# ADC-DAC.net
KiCad netlist of a schematic drawn in Altium Designer
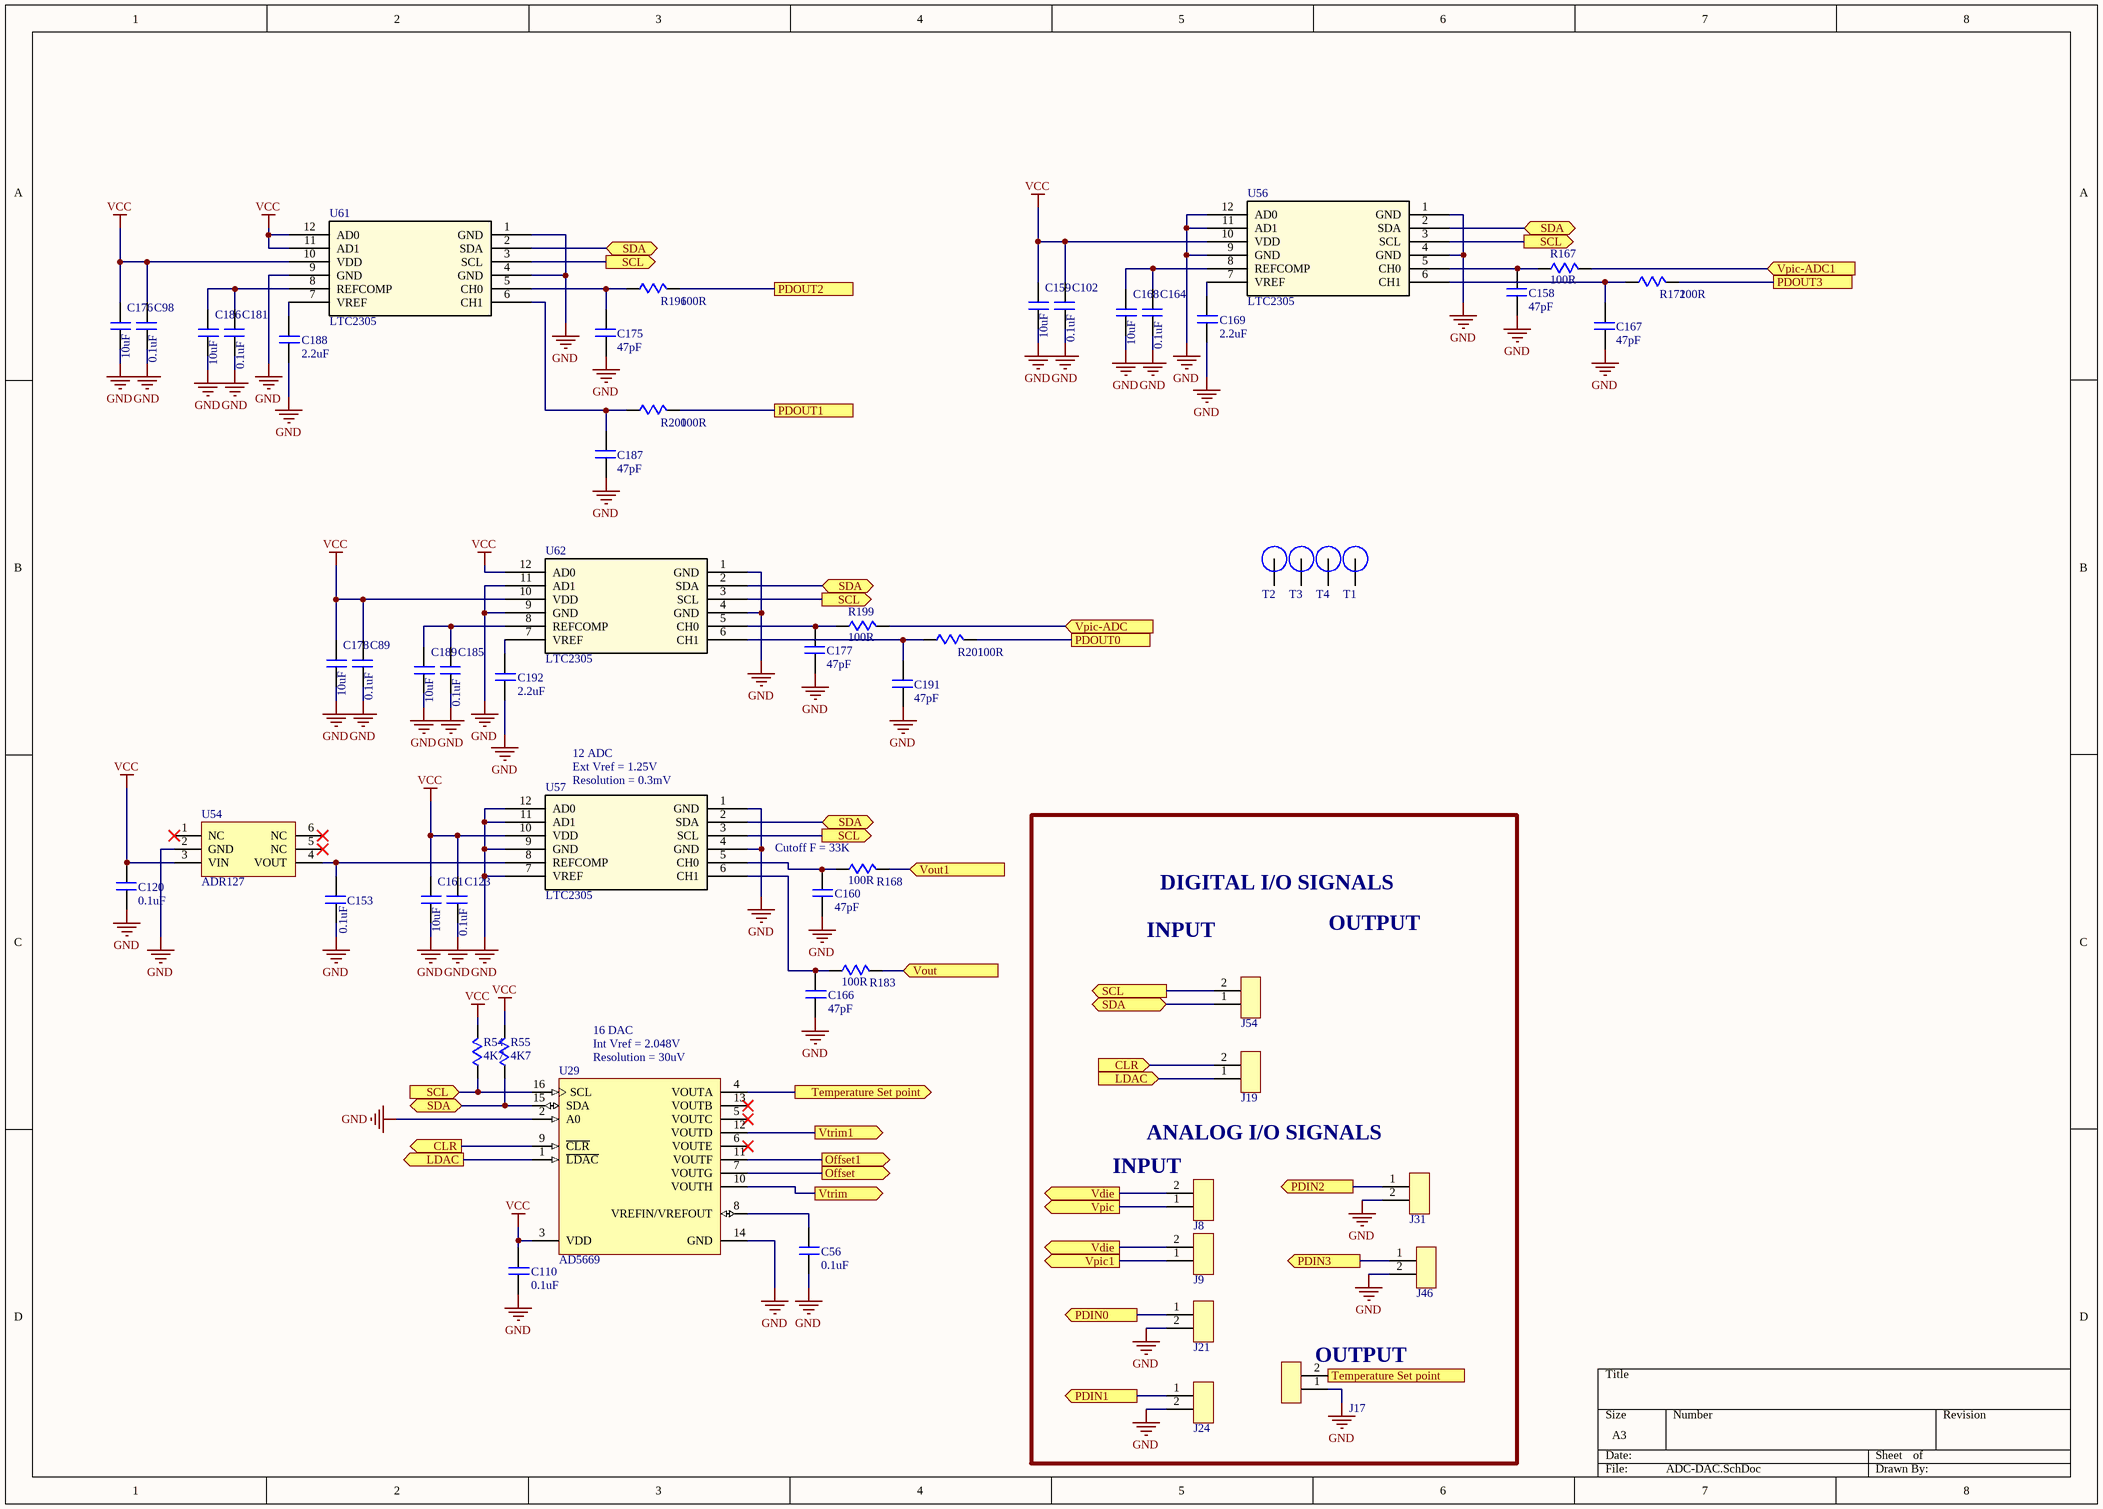
[diagram p0: ADC-DAC.SchDoc]

(export (version "E")
  (design (tool "Eeschema 10.0.6"))
  (components
    (comp (ref "C56")
      (value "0.1uF")
      (footprint "CAP0603")
      (description "50V 100nF X5R 卤10% 0603 Multilayer Ceramic Capacitors MLCC - SMD/SMT ROHS")
      (fields
        (field (name "MANUFACTURER") "TDK")
        (field (name "MANUFACTURER PART NUMBER") "C1608X5R1H104K080AA")
      )
      (libsource (lib "Pilot") (part "Capacitor 0.1uF"))
    )
    (comp (ref "C89")
      (value "0.1uF")
      (footprint "CAP0603")
      (description "50V 100nF X5R 卤10% 0603 Multilayer Ceramic Capacitors MLCC - SMD/SMT ROHS")
      (fields
        (field (name "MANUFACTURER") "TDK")
        (field (name "MANUFACTURER PART NUMBER") "C1608X5R1H104K080AA")
      )
      (libsource (lib "Pilot") (part "Capacitor 0.1uF"))
    )
    (comp (ref "C98")
      (value "0.1uF")
      (footprint "CAP0603")
      (description "50V 100nF X5R 卤10% 0603 Multilayer Ceramic Capacitors MLCC - SMD/SMT ROHS")
      (fields
        (field (name "MANUFACTURER") "TDK")
        (field (name "MANUFACTURER PART NUMBER") "C1608X5R1H104K080AA")
      )
      (libsource (lib "Pilot") (part "Capacitor 0.1uF"))
    )
    (comp (ref "C102")
      (value "0.1uF")
      (footprint "CAP0603")
      (description "50V 100nF X5R 卤10% 0603 Multilayer Ceramic Capacitors MLCC - SMD/SMT ROHS")
      (fields
        (field (name "MANUFACTURER") "TDK")
        (field (name "MANUFACTURER PART NUMBER") "C1608X5R1H104K080AA")
      )
      (libsource (lib "Pilot") (part "Capacitor 0.1uF"))
    )
    (comp (ref "C110")
      (value "0.1uF")
      (footprint "CAP0603")
      (description "50V 100nF X5R 卤10% 0603 Multilayer Ceramic Capacitors MLCC - SMD/SMT ROHS")
      (fields
        (field (name "MANUFACTURER") "TDK")
        (field (name "MANUFACTURER PART NUMBER") "C1608X5R1H104K080AA")
      )
      (libsource (lib "Pilot") (part "Capacitor 0.1uF"))
    )
    (comp (ref "C120")
      (value "0.1uF")
      (footprint "CAP0603")
      (description "50V 100nF X5R 卤10% 0603 Multilayer Ceramic Capacitors MLCC - SMD/SMT ROHS")
      (fields
        (field (name "MANUFACTURER") "TDK")
        (field (name "MANUFACTURER PART NUMBER") "C1608X5R1H104K080AA")
      )
      (libsource (lib "Pilot") (part "Capacitor 0.1uF"))
    )
    (comp (ref "C123")
      (value "0.1uF")
      (footprint "CAP0603")
      (description "50V 100nF X5R 卤10% 0603 Multilayer Ceramic Capacitors MLCC - SMD/SMT ROHS")
      (fields
        (field (name "MANUFACTURER") "TDK")
        (field (name "MANUFACTURER PART NUMBER") "C1608X5R1H104K080AA")
      )
      (libsource (lib "Pilot") (part "Capacitor 0.1uF"))
    )
    (comp (ref "C153")
      (value "0.1uF")
      (footprint "CAP0603")
      (description "50V 100nF X5R 卤10% 0603 Multilayer Ceramic Capacitors MLCC - SMD/SMT ROHS")
      (fields
        (field (name "MANUFACTURER") "TDK")
        (field (name "MANUFACTURER PART NUMBER") "C1608X5R1H104K080AA")
      )
      (libsource (lib "Pilot") (part "Capacitor 0.1uF"))
    )
    (comp (ref "C158")
      (value "47pF")
      (footprint "CAP0805")
      (description "Cap Cer 4.7PF 100V C0G/NP0 0805")
      (fields
        (field (name "MANUFACTURER") "Wurth Electronics")
        (field (name "MANUFACTURER PART NUMBER") "885012007096")
      )
      (libsource (lib "Pilot") (part "Capactior 47pF"))
    )
    (comp (ref "C159")
      (value "10uF")
      (footprint "CAP0805")
      (description "SMD Multilayer Ceramic Capacitor, 10 ï¿½F, 25 V, 0805 [2012 Metric], ï¿½ 10%, X7S")
      (fields
        (field (name "MANUFACTURER") "TDK")
        (field (name "MANUFACTURER PART NUMBER") "C2012X7S1E106K125AC")
      )
      (libsource (lib "Pilot") (part "Capacitor 10uF"))
    )
    (comp (ref "C160")
      (value "47pF")
      (footprint "CAP0805")
      (description "Cap Cer 4.7PF 100V C0G/NP0 0805")
      (fields
        (field (name "MANUFACTURER") "Wurth Electronics")
        (field (name "MANUFACTURER PART NUMBER") "885012007096")
      )
      (libsource (lib "Pilot") (part "Capactior 47pF"))
    )
    (comp (ref "C161")
      (value "10uF")
      (footprint "CAP0805")
      (description "SMD Multilayer Ceramic Capacitor, 10 ï¿½F, 25 V, 0805 [2012 Metric], ï¿½ 10%, X7S")
      (fields
        (field (name "MANUFACTURER") "TDK")
        (field (name "MANUFACTURER PART NUMBER") "C2012X7S1E106K125AC")
      )
      (libsource (lib "Pilot") (part "Capacitor 10uF"))
    )
    (comp (ref "C164")
      (value "0.1uF")
      (footprint "CAP0603")
      (description "50V 100nF X5R 卤10% 0603 Multilayer Ceramic Capacitors MLCC - SMD/SMT ROHS")
      (fields
        (field (name "MANUFACTURER") "TDK")
        (field (name "MANUFACTURER PART NUMBER") "C1608X5R1H104K080AA")
      )
      (libsource (lib "Pilot") (part "Capacitor 0.1uF"))
    )
    (comp (ref "C166")
      (value "47pF")
      (footprint "CAP0805")
      (description "Cap Cer 4.7PF 100V C0G/NP0 0805")
      (fields
        (field (name "MANUFACTURER") "Wurth Electronics")
        (field (name "MANUFACTURER PART NUMBER") "885012007096")
      )
      (libsource (lib "Pilot") (part "Capactior 47pF"))
    )
    (comp (ref "C167")
      (value "47pF")
      (footprint "CAP0805")
      (description "Cap Cer 4.7PF 100V C0G/NP0 0805")
      (fields
        (field (name "MANUFACTURER") "Wurth Electronics")
        (field (name "MANUFACTURER PART NUMBER") "885012007096")
      )
      (libsource (lib "Pilot") (part "Capactior 47pF"))
    )
    (comp (ref "C168")
      (value "10uF")
      (footprint "CAP0805")
      (description "SMD Multilayer Ceramic Capacitor, 10 ï¿½F, 25 V, 0805 [2012 Metric], ï¿½ 10%, X7S")
      (fields
        (field (name "MANUFACTURER") "TDK")
        (field (name "MANUFACTURER PART NUMBER") "C2012X7S1E106K125AC")
      )
      (libsource (lib "Pilot") (part "Capacitor 10uF"))
    )
    (comp (ref "C169")
      (value "2.2uF")
      (footprint "CAP0603")
      (description "Multilayer Ceramic Capacitors (High dielectric type), 16V, 2.2 uF, ± 20 %, 0603, X5R, RoHS")
      (fields
        (field (name "MANUFACTURER") "Taiyo Yuden")
        (field (name "MANUFACTURER PART NUMBER") "EMK107BJ225MA-T")
      )
      (libsource (lib "Pilot") (part "Capacitor 2.2uF"))
    )
    (comp (ref "C175")
      (value "47pF")
      (footprint "CAP0805")
      (description "Cap Cer 4.7PF 100V C0G/NP0 0805")
      (fields
        (field (name "MANUFACTURER") "Wurth Electronics")
        (field (name "MANUFACTURER PART NUMBER") "885012007096")
      )
      (libsource (lib "Pilot") (part "Capactior 47pF"))
    )
    (comp (ref "C176")
      (value "10uF")
      (footprint "CAP0805")
      (description "SMD Multilayer Ceramic Capacitor, 10 ï¿½F, 25 V, 0805 [2012 Metric], ï¿½ 10%, X7S")
      (fields
        (field (name "MANUFACTURER") "TDK")
        (field (name "MANUFACTURER PART NUMBER") "C2012X7S1E106K125AC")
      )
      (libsource (lib "Pilot") (part "Capacitor 10uF"))
    )
    (comp (ref "C177")
      (value "47pF")
      (footprint "CAP0805")
      (description "Cap Cer 4.7PF 100V C0G/NP0 0805")
      (fields
        (field (name "MANUFACTURER") "Wurth Electronics")
        (field (name "MANUFACTURER PART NUMBER") "885012007096")
      )
      (libsource (lib "Pilot") (part "Capactior 47pF"))
    )
    (comp (ref "C178")
      (value "10uF")
      (footprint "CAP0805")
      (description "SMD Multilayer Ceramic Capacitor, 10 ï¿½F, 25 V, 0805 [2012 Metric], ï¿½ 10%, X7S")
      (fields
        (field (name "MANUFACTURER") "TDK")
        (field (name "MANUFACTURER PART NUMBER") "C2012X7S1E106K125AC")
      )
      (libsource (lib "Pilot") (part "Capacitor 10uF"))
    )
    (comp (ref "C181")
      (value "0.1uF")
      (footprint "CAP0603")
      (description "50V 100nF X5R 卤10% 0603 Multilayer Ceramic Capacitors MLCC - SMD/SMT ROHS")
      (fields
        (field (name "MANUFACTURER") "TDK")
        (field (name "MANUFACTURER PART NUMBER") "C1608X5R1H104K080AA")
      )
      (libsource (lib "Pilot") (part "Capacitor 0.1uF"))
    )
    (comp (ref "C185")
      (value "0.1uF")
      (footprint "CAP0603")
      (description "50V 100nF X5R 卤10% 0603 Multilayer Ceramic Capacitors MLCC - SMD/SMT ROHS")
      (fields
        (field (name "MANUFACTURER") "TDK")
        (field (name "MANUFACTURER PART NUMBER") "C1608X5R1H104K080AA")
      )
      (libsource (lib "Pilot") (part "Capacitor 0.1uF"))
    )
    (comp (ref "C186")
      (value "10uF")
      (footprint "CAP0805")
      (description "SMD Multilayer Ceramic Capacitor, 10 ï¿½F, 25 V, 0805 [2012 Metric], ï¿½ 10%, X7S")
      (fields
        (field (name "MANUFACTURER") "TDK")
        (field (name "MANUFACTURER PART NUMBER") "C2012X7S1E106K125AC")
      )
      (libsource (lib "Pilot") (part "Capacitor 10uF"))
    )
    (comp (ref "C187")
      (value "47pF")
      (footprint "CAP0805")
      (description "Cap Cer 4.7PF 100V C0G/NP0 0805")
      (fields
        (field (name "MANUFACTURER") "Wurth Electronics")
        (field (name "MANUFACTURER PART NUMBER") "885012007096")
      )
      (libsource (lib "Pilot") (part "Capactior 47pF"))
    )
    (comp (ref "C188")
      (value "2.2uF")
      (footprint "CAP0603")
      (description "Multilayer Ceramic Capacitors (High dielectric type), 16V, 2.2 uF, ± 20 %, 0603, X5R, RoHS")
      (fields
        (field (name "MANUFACTURER") "Taiyo Yuden")
        (field (name "MANUFACTURER PART NUMBER") "EMK107BJ225MA-T")
      )
      (libsource (lib "Pilot") (part "Capacitor 2.2uF"))
    )
    (comp (ref "C189")
      (value "10uF")
      (footprint "CAP0805")
      (description "SMD Multilayer Ceramic Capacitor, 10 ï¿½F, 25 V, 0805 [2012 Metric], ï¿½ 10%, X7S")
      (fields
        (field (name "MANUFACTURER") "TDK")
        (field (name "MANUFACTURER PART NUMBER") "C2012X7S1E106K125AC")
      )
      (libsource (lib "Pilot") (part "Capacitor 10uF"))
    )
    (comp (ref "C191")
      (value "47pF")
      (footprint "CAP0805")
      (description "Cap Cer 4.7PF 100V C0G/NP0 0805")
      (fields
        (field (name "MANUFACTURER") "Wurth Electronics")
        (field (name "MANUFACTURER PART NUMBER") "885012007096")
      )
      (libsource (lib "Pilot") (part "Capactior 47pF"))
    )
    (comp (ref "C192")
      (value "2.2uF")
      (footprint "CAP0603")
      (description "Multilayer Ceramic Capacitors (High dielectric type), 16V, 2.2 uF, ± 20 %, 0603, X5R, RoHS")
      (fields
        (field (name "MANUFACTURER") "Taiyo Yuden")
        (field (name "MANUFACTURER PART NUMBER") "EMK107BJ225MA-T")
      )
      (libsource (lib "Pilot") (part "Capacitor 2.2uF"))
    )
    (comp (ref "J8")
      (value "Header1x2")
      (footprint "HEADER 1x2")
      (description "Conn Wire to Board HDR 2 POS 2.54mm Solder ST Thru-Hole Bulk")
      (fields (field (name "MANUFACTURER") "Molex") (field (name "MANUFACTURER PART NUMBER") "22-23-2022"))
      (libsource (lib "") (part "Header 1x2_1"))
    )
    (comp (ref "J9")
      (value "Header1x2")
      (footprint "HEADER 1x2")
      (description "Conn Wire to Board HDR 2 POS 2.54mm Solder ST Thru-Hole Bulk")
      (fields (field (name "MANUFACTURER") "Molex") (field (name "MANUFACTURER PART NUMBER") "22-23-2022"))
      (libsource (lib "") (part "Header 1x2_1"))
    )
    (comp (ref "J17")
      (value "Header1x2")
      (footprint "HEADER 1x2")
      (description "Conn Wire to Board HDR 2 POS 2.54mm Solder ST Thru-Hole Bulk")
      (fields (field (name "MANUFACTURER") "Molex") (field (name "MANUFACTURER PART NUMBER") "22-23-2022"))
      (libsource (lib "") (part "Header 1x2_2"))
    )
    (comp (ref "J19")
      (value "Header1x2")
      (footprint "HEADER 1x2")
      (description "Conn Wire to Board HDR 2 POS 2.54mm Solder ST Thru-Hole Bulk")
      (fields (field (name "MANUFACTURER") "Molex") (field (name "MANUFACTURER PART NUMBER") "22-23-2022"))
      (libsource (lib "") (part "Header 1x2_1"))
    )
    (comp (ref "J21")
      (value "Header1x2")
      (footprint "HEADER 1x2")
      (description "Conn Wire to Board HDR 2 POS 2.54mm Solder ST Thru-Hole Bulk")
      (fields (field (name "MANUFACTURER") "Molex") (field (name "MANUFACTURER PART NUMBER") "22-23-2022"))
      (libsource (lib "Pilot") (part "Header 1x2"))
    )
    (comp (ref "J24")
      (value "Header1x2")
      (footprint "HEADER 1x2")
      (description "Conn Wire to Board HDR 2 POS 2.54mm Solder ST Thru-Hole Bulk")
      (fields (field (name "MANUFACTURER") "Molex") (field (name "MANUFACTURER PART NUMBER") "22-23-2022"))
      (libsource (lib "Pilot") (part "Header 1x2"))
    )
    (comp (ref "J31")
      (value "Header1x2")
      (footprint "HEADER 1x2")
      (description "Conn Wire to Board HDR 2 POS 2.54mm Solder ST Thru-Hole Bulk")
      (fields (field (name "MANUFACTURER") "Molex") (field (name "MANUFACTURER PART NUMBER") "22-23-2022"))
      (libsource (lib "Pilot") (part "Header 1x2"))
    )
    (comp (ref "J46")
      (value "Header1x2")
      (footprint "HEADER 1x2")
      (description "Conn Wire to Board HDR 2 POS 2.54mm Solder ST Thru-Hole Bulk")
      (fields (field (name "MANUFACTURER") "Molex") (field (name "MANUFACTURER PART NUMBER") "22-23-2022"))
      (libsource (lib "Pilot") (part "Header 1x2"))
    )
    (comp (ref "J54")
      (value "Header1x2")
      (footprint "HEADER 1x2")
      (description "Conn Wire to Board HDR 2 POS 2.54mm Solder ST Thru-Hole Bulk")
      (fields (field (name "MANUFACTURER") "Molex") (field (name "MANUFACTURER PART NUMBER") "22-23-2022"))
      (libsource (lib "") (part "Header 1x2_1"))
    )
    (comp (ref "R54")
      (value "4K7")
      (footprint "RES0805")
      (description "Res Thin Film 0805 4.7K Ohm 0.1% 0.125W(1/8W) ±50ppm/C Epoxy Pad SMD T/R")
      (fields
        (field (name "MANUFACTURER") "Yageo")
        (field (name "MANUFACTURER PART NUMBER") "RT0805BRE074K7L")
      )
      (libsource (lib "Pilot") (part "Resistor 4.7K"))
    )
    (comp (ref "R55")
      (value "4K7")
      (footprint "RES0805")
      (description "Res Thin Film 0805 4.7K Ohm 0.1% 0.125W(1/8W) ±50ppm/C Epoxy Pad SMD T/R")
      (fields
        (field (name "MANUFACTURER") "Yageo")
        (field (name "MANUFACTURER PART NUMBER") "RT0805BRE074K7L")
      )
      (libsource (lib "Pilot") (part "Resistor 4.7K"))
    )
    (comp (ref "R167")
      (value "100R")
      (footprint "RES0805")
      (description "High Precision-High Stability Chip Resistor Thin Film 0805 100Ohm 0.5% Paper T/R")
      (fields
        (field (name "MANUFACTURER") "Yageo")
        (field (name "MANUFACTURER PART NUMBER") "RT0805DRE07100RL")
      )
      (libsource (lib "Pilot") (part "Resistor 100R"))
    )
    (comp (ref "R168")
      (value "100R")
      (footprint "RES0805")
      (description "High Precision-High Stability Chip Resistor Thin Film 0805 100Ohm 0.5% Paper T/R")
      (fields
        (field (name "MANUFACTURER") "Yageo")
        (field (name "MANUFACTURER PART NUMBER") "RT0805DRE07100RL")
      )
      (libsource (lib "Pilot") (part "Resistor 100R"))
    )
    (comp (ref "R172")
      (value "100R")
      (footprint "RES0805")
      (description "High Precision-High Stability Chip Resistor Thin Film 0805 100Ohm 0.5% Paper T/R")
      (fields
        (field (name "MANUFACTURER") "Yageo")
        (field (name "MANUFACTURER PART NUMBER") "RT0805DRE07100RL")
      )
      (libsource (lib "Pilot") (part "Resistor 100R"))
    )
    (comp (ref "R183")
      (value "100R")
      (footprint "RES0805")
      (description "High Precision-High Stability Chip Resistor Thin Film 0805 100Ohm 0.5% Paper T/R")
      (fields
        (field (name "MANUFACTURER") "Yageo")
        (field (name "MANUFACTURER PART NUMBER") "RT0805DRE07100RL")
      )
      (libsource (lib "Pilot") (part "Resistor 100R"))
    )
    (comp (ref "R196")
      (value "100R")
      (footprint "RES0805")
      (description "High Precision-High Stability Chip Resistor Thin Film 0805 100Ohm 0.5% Paper T/R")
      (fields
        (field (name "MANUFACTURER") "Yageo")
        (field (name "MANUFACTURER PART NUMBER") "RT0805DRE07100RL")
      )
      (libsource (lib "Pilot") (part "Resistor 100R"))
    )
    (comp (ref "R199")
      (value "100R")
      (footprint "RES0805")
      (description "High Precision-High Stability Chip Resistor Thin Film 0805 100Ohm 0.5% Paper T/R")
      (fields
        (field (name "MANUFACTURER") "Yageo")
        (field (name "MANUFACTURER PART NUMBER") "RT0805DRE07100RL")
      )
      (libsource (lib "Pilot") (part "Resistor 100R"))
    )
    (comp (ref "R200")
      (value "100R")
      (footprint "RES0805")
      (description "High Precision-High Stability Chip Resistor Thin Film 0805 100Ohm 0.5% Paper T/R")
      (fields
        (field (name "MANUFACTURER") "Yageo")
        (field (name "MANUFACTURER PART NUMBER") "RT0805DRE07100RL")
      )
      (libsource (lib "Pilot") (part "Resistor 100R"))
    )
    (comp (ref "R201")
      (value "100R")
      (footprint "RES0805")
      (description "High Precision-High Stability Chip Resistor Thin Film 0805 100Ohm 0.5% Paper T/R")
      (fields
        (field (name "MANUFACTURER") "Yageo")
        (field (name "MANUFACTURER PART NUMBER") "RT0805DRE07100RL")
      )
      (libsource (lib "Pilot") (part "Resistor 100R"))
    )
    (comp (ref "T1")
      (value "TP")
      (footprint "Hole 3.3mm")
      (libsource (lib "Pilot") (part "Mount hole 3.3mm"))
    )
    (comp (ref "T2")
      (value "TP")
      (footprint "Hole 3.3mm")
      (libsource (lib "Pilot") (part "Mount hole 3.3mm"))
    )
    (comp (ref "T3")
      (value "TP")
      (footprint "Hole 3.3mm")
      (libsource (lib "Pilot") (part "Mount hole 3.3mm"))
    )
    (comp (ref "T4")
      (value "TP")
      (footprint "Hole 3.3mm")
      (libsource (lib "Pilot") (part "Mount hole 3.3mm"))
    )
    (comp (ref "U29")
      (value "AD5669")
      (footprint "TSSOP16")
      (description "DAC 8-CH Resistor-String 16-bit 16-Pin TSSOP Tube")
      (fields
        (field (name "MANUFACTURER") "Analog Devices")
        (field (name "MANUFACTURER PART NUMBER") "AD5669RARUZ-1")
      )
      (libsource (lib "Pilot") (part "AD5669RARUZ-1"))
    )
    (comp (ref "U54")
      (value "ADR127")
      (footprint "TSOT6")
      (description "Precision, Micropower LD0 1.25 VOUT Voltage Reference in TSOT")
      (fields
        (field (name "MANUFACTURER") "Analog Devices")
        (field (name "MANUFACTURER PART NUMBER") "ADR127BUJZ-REEL7")
      )
      (libsource (lib "Pilot") (part "ADR127BUJZ-REEL7"))
    )
    (comp (ref "U56")
      (value "LTC2305")
      (footprint "MSOP12")
      (description "2-Channel Single ADC SAR 14ksps 12-bit Serial Automotive 12-Pin MSOP Tube")
      (fields
        (field (name "MANUFACTURER") "Analog Devices / Linear Technology")
        (field (name "MANUFACTURER PART NUMBER") "LTC2305CMS#PBF")
      )
      (libsource (lib "Pilot") (part "LTC2305CMS#PBF"))
    )
    (comp (ref "U57")
      (value "LTC2305")
      (footprint "MSOP12")
      (description "2-Channel Single ADC SAR 14ksps 12-bit Serial Automotive 12-Pin MSOP Tube")
      (fields
        (field (name "MANUFACTURER") "Analog Devices / Linear Technology")
        (field (name "MANUFACTURER PART NUMBER") "LTC2305CMS#PBF")
      )
      (libsource (lib "Pilot") (part "LTC2305CMS#PBF"))
    )
    (comp (ref "U61")
      (value "LTC2305")
      (footprint "MSOP12")
      (description "2-Channel Single ADC SAR 14ksps 12-bit Serial Automotive 12-Pin MSOP Tube")
      (fields
        (field (name "MANUFACTURER") "Analog Devices / Linear Technology")
        (field (name "MANUFACTURER PART NUMBER") "LTC2305CMS#PBF")
      )
      (libsource (lib "Pilot") (part "LTC2305CMS#PBF"))
    )
    (comp (ref "U62")
      (value "LTC2305")
      (footprint "MSOP12")
      (description "2-Channel Single ADC SAR 14ksps 12-bit Serial Automotive 12-Pin MSOP Tube")
      (fields
        (field (name "MANUFACTURER") "Analog Devices / Linear Technology")
        (field (name "MANUFACTURER PART NUMBER") "LTC2305CMS#PBF")
      )
      (libsource (lib "Pilot") (part "LTC2305CMS#PBF"))
    )
  )
  (nets
    (net (code "1") (name "/CLR") (class "Default")
      (node (ref "J19") (pin "2") (pinfunction "2_2") (pintype "passive"))
      (node (ref "U29") (pin "9") (pinfunction "~{CLR}_9") (pintype "input"))
    )
    (net (code "2") (name "/LDAC") (class "Default")
      (node (ref "J19") (pin "1") (pinfunction "1_1") (pintype "passive"))
      (node (ref "U29") (pin "1") (pinfunction "~{LDAC}_1") (pintype "input"))
    )
    (net (code "3") (name "/Offset") (class "Default")
      (node (ref "U29") (pin "7") (pinfunction "VOUTG_7") (pintype "tri_state"))
    )
    (net (code "4") (name "/Offset1") (class "Default")
      (node (ref "U29") (pin "11") (pinfunction "VOUTF_11") (pintype "tri_state"))
    )
    (net (code "5") (name "/PDIN0") (class "Default")
      (node (ref "J21") (pin "1") (pinfunction "1_1") (pintype "passive"))
    )
    (net (code "6") (name "/PDIN1") (class "Default")
      (node (ref "J24") (pin "1") (pinfunction "1_1") (pintype "passive"))
    )
    (net (code "7") (name "/PDIN2") (class "Default")
      (node (ref "J31") (pin "1") (pinfunction "1_1") (pintype "passive"))
    )
    (net (code "8") (name "/PDIN3") (class "Default")
      (node (ref "J46") (pin "1") (pinfunction "1_1") (pintype "passive"))
    )
    (net (code "9") (name "/PDOUT0") (class "Default")
      (node (ref "R201") (pin "2") (pinfunction "2_2") (pintype "passive"))
    )
    (net (code "10") (name "/PDOUT1") (class "Default")
      (node (ref "R200") (pin "2") (pinfunction "2_2") (pintype "passive"))
    )
    (net (code "11") (name "/PDOUT2") (class "Default")
      (node (ref "R196") (pin "2") (pinfunction "2_2") (pintype "passive"))
    )
    (net (code "12") (name "/PDOUT3") (class "Default")
      (node (ref "R172") (pin "2") (pinfunction "2_2") (pintype "passive"))
    )
    (net (code "13") (name "/SCL") (class "Default")
      (node (ref "J54") (pin "2") (pinfunction "2_2") (pintype "passive"))
      (node (ref "R54") (pin "1") (pinfunction "1_1") (pintype "passive"))
      (node (ref "U29") (pin "16") (pinfunction "SCL_16") (pintype "input"))
      (node (ref "U56") (pin "3") (pinfunction "SCL_3") (pintype "passive"))
      (node (ref "U57") (pin "3") (pinfunction "SCL_3") (pintype "passive"))
      (node (ref "U61") (pin "3") (pinfunction "SCL_3") (pintype "passive"))
      (node (ref "U62") (pin "3") (pinfunction "SCL_3") (pintype "passive"))
    )
    (net (code "14") (name "/SDA") (class "Default")
      (node (ref "J54") (pin "1") (pinfunction "1_1") (pintype "passive"))
      (node (ref "R55") (pin "1") (pinfunction "1_1") (pintype "passive"))
      (node (ref "U29") (pin "15") (pinfunction "SDA_15") (pintype "bidirectional"))
      (node (ref "U56") (pin "2") (pinfunction "SDA_2") (pintype "passive"))
      (node (ref "U57") (pin "2") (pinfunction "SDA_2") (pintype "passive"))
      (node (ref "U61") (pin "2") (pinfunction "SDA_2") (pintype "passive"))
      (node (ref "U62") (pin "2") (pinfunction "SDA_2") (pintype "passive"))
    )
    (net (code "15") (name "/Temperature Set point") (class "Default")
      (node (ref "J17") (pin "2") (pinfunction "2_2") (pintype "passive"))
      (node (ref "U29") (pin "4") (pinfunction "VOUTA_4") (pintype "tri_state"))
    )
    (net (code "16") (name "/Vdie") (class "Default")
      (node (ref "J8") (pin "2") (pinfunction "2_2") (pintype "passive"))
      (node (ref "J9") (pin "2") (pinfunction "2_2") (pintype "passive"))
    )
    (net (code "17") (name "/Vout") (class "Default")
      (node (ref "R183") (pin "2") (pinfunction "2_2") (pintype "passive"))
    )
    (net (code "18") (name "/Vout1") (class "Default")
      (node (ref "R168") (pin "2") (pinfunction "2_2") (pintype "passive"))
    )
    (net (code "19") (name "/Vpic") (class "Default")
      (node (ref "J8") (pin "1") (pinfunction "1_1") (pintype "passive"))
    )
    (net (code "20") (name "/Vpic-ADC") (class "Default")
      (node (ref "R199") (pin "2") (pinfunction "2_2") (pintype "passive"))
    )
    (net (code "21") (name "/Vpic-ADC1") (class "Default")
      (node (ref "R167") (pin "2") (pinfunction "2_2") (pintype "passive"))
    )
    (net (code "22") (name "/Vpic1") (class "Default")
      (node (ref "J9") (pin "1") (pinfunction "1_1") (pintype "passive"))
    )
    (net (code "23") (name "/Vtrim") (class "Default")
      (node (ref "U29") (pin "10") (pinfunction "VOUTH_10") (pintype "tri_state"))
    )
    (net (code "24") (name "/Vtrim1") (class "Default")
      (node (ref "U29") (pin "12") (pinfunction "VOUTD_12") (pintype "tri_state"))
    )
    (net (code "25") (name "GND") (class "Default")
      (node (ref "C102") (pin "2") (pinfunction "2_2") (pintype "passive"))
      (node (ref "C110") (pin "2") (pinfunction "2_2") (pintype "passive"))
      (node (ref "C120") (pin "2") (pinfunction "2_2") (pintype "passive"))
      (node (ref "C123") (pin "2") (pinfunction "2_2") (pintype "passive"))
      (node (ref "C153") (pin "2") (pinfunction "2_2") (pintype "passive"))
      (node (ref "C158") (pin "1") (pinfunction "1_1") (pintype "passive"))
      (node (ref "C159") (pin "2") (pinfunction "2_2") (pintype "passive"))
      (node (ref "C160") (pin "2") (pinfunction "2_2") (pintype "passive"))
      (node (ref "C161") (pin "2") (pinfunction "2_2") (pintype "passive"))
      (node (ref "C164") (pin "2") (pinfunction "2_2") (pintype "passive"))
      (node (ref "C166") (pin "2") (pinfunction "2_2") (pintype "passive"))
      (node (ref "C167") (pin "1") (pinfunction "1_1") (pintype "passive"))
      (node (ref "C168") (pin "2") (pinfunction "2_2") (pintype "passive"))
      (node (ref "C169") (pin "2") (pinfunction "2_2") (pintype "passive"))
      (node (ref "C175") (pin "1") (pinfunction "1_1") (pintype "passive"))
      (node (ref "C176") (pin "2") (pinfunction "2_2") (pintype "passive"))
      (node (ref "C177") (pin "1") (pinfunction "1_1") (pintype "passive"))
      (node (ref "C178") (pin "2") (pinfunction "2_2") (pintype "passive"))
      (node (ref "C181") (pin "2") (pinfunction "2_2") (pintype "passive"))
      (node (ref "C185") (pin "2") (pinfunction "2_2") (pintype "passive"))
      (node (ref "C186") (pin "2") (pinfunction "2_2") (pintype "passive"))
      (node (ref "C187") (pin "1") (pinfunction "1_1") (pintype "passive"))
      (node (ref "C188") (pin "2") (pinfunction "2_2") (pintype "passive"))
      (node (ref "C189") (pin "2") (pinfunction "2_2") (pintype "passive"))
      (node (ref "C191") (pin "1") (pinfunction "1_1") (pintype "passive"))
      (node (ref "C192") (pin "2") (pinfunction "2_2") (pintype "passive"))
      (node (ref "C56") (pin "2") (pinfunction "2_2") (pintype "passive"))
      (node (ref "C89") (pin "2") (pinfunction "2_2") (pintype "passive"))
      (node (ref "C98") (pin "2") (pinfunction "2_2") (pintype "passive"))
      (node (ref "J17") (pin "1") (pinfunction "1_1") (pintype "passive"))
      (node (ref "J21") (pin "2") (pinfunction "2_2") (pintype "passive"))
      (node (ref "J24") (pin "2") (pinfunction "2_2") (pintype "passive"))
      (node (ref "J31") (pin "2") (pinfunction "2_2") (pintype "passive"))
      (node (ref "J46") (pin "2") (pinfunction "2_2") (pintype "passive"))
      (node (ref "U29") (pin "14") (pinfunction "GND_14") (pintype "power_in"))
      (node (ref "U29") (pin "2") (pinfunction "A0_2") (pintype "input"))
      (node (ref "U54") (pin "2") (pinfunction "GND_2") (pintype "passive"))
      (node (ref "U56") (pin "1") (pinfunction "GND_1") (pintype "passive"))
      (node (ref "U56") (pin "11") (pinfunction "AD1_11") (pintype "passive"))
      (node (ref "U56") (pin "12") (pinfunction "AD0_12") (pintype "passive"))
      (node (ref "U56") (pin "4") (pinfunction "GND_4") (pintype "power_in"))
      (node (ref "U56") (pin "9") (pinfunction "GND_9") (pintype "power_in"))
      (node (ref "U57") (pin "1") (pinfunction "GND_1") (pintype "passive"))
      (node (ref "U57") (pin "11") (pinfunction "AD1_11") (pintype "passive"))
      (node (ref "U57") (pin "12") (pinfunction "AD0_12") (pintype "passive"))
      (node (ref "U57") (pin "4") (pinfunction "GND_4") (pintype "power_in"))
      (node (ref "U57") (pin "7") (pinfunction "VREF_7") (pintype "passive"))
      (node (ref "U57") (pin "9") (pinfunction "GND_9") (pintype "power_in"))
      (node (ref "U61") (pin "1") (pinfunction "GND_1") (pintype "passive"))
      (node (ref "U61") (pin "4") (pinfunction "GND_4") (pintype "power_in"))
      (node (ref "U61") (pin "9") (pinfunction "GND_9") (pintype "power_in"))
      (node (ref "U62") (pin "1") (pinfunction "GND_1") (pintype "passive"))
      (node (ref "U62") (pin "11") (pinfunction "AD1_11") (pintype "passive"))
      (node (ref "U62") (pin "4") (pinfunction "GND_4") (pintype "power_in"))
      (node (ref "U62") (pin "9") (pinfunction "GND_9") (pintype "power_in"))
    )
    (net (code "26") (name "Net-(U29-VREFIN{slash}VREFOUT)") (class "Default")
      (node (ref "C56") (pin "1") (pinfunction "1_1") (pintype "passive"))
      (node (ref "U29") (pin "8") (pinfunction "VREFIN/VREFOUT_8") (pintype "bidirectional"))
    )
    (net (code "27") (name "Net-(U54-VOUT)") (class "Default")
      (node (ref "C153") (pin "1") (pinfunction "1_1") (pintype "passive"))
      (node (ref "U54") (pin "4") (pinfunction "VOUT_4") (pintype "passive"))
      (node (ref "U57") (pin "8") (pinfunction "REFCOMP_8") (pintype "passive"))
    )
    (net (code "28") (name "Net-(U56-CH0)") (class "Default")
      (node (ref "C158") (pin "2") (pinfunction "2_2") (pintype "passive"))
      (node (ref "R167") (pin "1") (pinfunction "1_1") (pintype "passive"))
      (node (ref "U56") (pin "5") (pinfunction "CH0_5") (pintype "passive"))
    )
    (net (code "29") (name "Net-(U56-CH1)") (class "Default")
      (node (ref "C167") (pin "2") (pinfunction "2_2") (pintype "passive"))
      (node (ref "R172") (pin "1") (pinfunction "1_1") (pintype "passive"))
      (node (ref "U56") (pin "6") (pinfunction "CH1_6") (pintype "passive"))
    )
    (net (code "30") (name "Net-(U56-REFCOMP)") (class "Default")
      (node (ref "C164") (pin "1") (pinfunction "1_1") (pintype "passive"))
      (node (ref "C168") (pin "1") (pinfunction "1_1") (pintype "passive"))
      (node (ref "U56") (pin "8") (pinfunction "REFCOMP_8") (pintype "passive"))
    )
    (net (code "31") (name "Net-(U56-VREF)") (class "Default")
      (node (ref "C169") (pin "1") (pinfunction "1_1") (pintype "passive"))
      (node (ref "U56") (pin "7") (pinfunction "VREF_7") (pintype "passive"))
    )
    (net (code "32") (name "Net-(U57-CH0)") (class "Default")
      (node (ref "C160") (pin "1") (pinfunction "1_1") (pintype "passive"))
      (node (ref "R168") (pin "1") (pinfunction "1_1") (pintype "passive"))
      (node (ref "U57") (pin "5") (pinfunction "CH0_5") (pintype "passive"))
    )
    (net (code "33") (name "Net-(U57-CH1)") (class "Default")
      (node (ref "C166") (pin "1") (pinfunction "1_1") (pintype "passive"))
      (node (ref "R183") (pin "1") (pinfunction "1_1") (pintype "passive"))
      (node (ref "U57") (pin "6") (pinfunction "CH1_6") (pintype "passive"))
    )
    (net (code "34") (name "Net-(U61-CH0)") (class "Default")
      (node (ref "C175") (pin "2") (pinfunction "2_2") (pintype "passive"))
      (node (ref "R196") (pin "1") (pinfunction "1_1") (pintype "passive"))
      (node (ref "U61") (pin "5") (pinfunction "CH0_5") (pintype "passive"))
    )
    (net (code "35") (name "Net-(U61-CH1)") (class "Default")
      (node (ref "C187") (pin "2") (pinfunction "2_2") (pintype "passive"))
      (node (ref "R200") (pin "1") (pinfunction "1_1") (pintype "passive"))
      (node (ref "U61") (pin "6") (pinfunction "CH1_6") (pintype "passive"))
    )
    (net (code "36") (name "Net-(U61-REFCOMP)") (class "Default")
      (node (ref "C181") (pin "1") (pinfunction "1_1") (pintype "passive"))
      (node (ref "C186") (pin "1") (pinfunction "1_1") (pintype "passive"))
      (node (ref "U61") (pin "8") (pinfunction "REFCOMP_8") (pintype "passive"))
    )
    (net (code "37") (name "Net-(U61-VREF)") (class "Default")
      (node (ref "C188") (pin "1") (pinfunction "1_1") (pintype "passive"))
      (node (ref "U61") (pin "7") (pinfunction "VREF_7") (pintype "passive"))
    )
    (net (code "38") (name "Net-(U62-CH0)") (class "Default")
      (node (ref "C177") (pin "2") (pinfunction "2_2") (pintype "passive"))
      (node (ref "R199") (pin "1") (pinfunction "1_1") (pintype "passive"))
      (node (ref "U62") (pin "5") (pinfunction "CH0_5") (pintype "passive"))
    )
    (net (code "39") (name "Net-(U62-CH1)") (class "Default")
      (node (ref "C191") (pin "2") (pinfunction "2_2") (pintype "passive"))
      (node (ref "R201") (pin "1") (pinfunction "1_1") (pintype "passive"))
      (node (ref "U62") (pin "6") (pinfunction "CH1_6") (pintype "passive"))
    )
    (net (code "40") (name "Net-(U62-REFCOMP)") (class "Default")
      (node (ref "C185") (pin "1") (pinfunction "1_1") (pintype "passive"))
      (node (ref "C189") (pin "1") (pinfunction "1_1") (pintype "passive"))
      (node (ref "U62") (pin "8") (pinfunction "REFCOMP_8") (pintype "passive"))
    )
    (net (code "41") (name "Net-(U62-VREF)") (class "Default")
      (node (ref "C192") (pin "1") (pinfunction "1_1") (pintype "passive"))
      (node (ref "U62") (pin "7") (pinfunction "VREF_7") (pintype "passive"))
    )
    (net (code "42") (name "VCC") (class "Default")
      (node (ref "C102") (pin "1") (pinfunction "1_1") (pintype "passive"))
      (node (ref "C110") (pin "1") (pinfunction "1_1") (pintype "passive"))
      (node (ref "C120") (pin "1") (pinfunction "1_1") (pintype "passive"))
      (node (ref "C123") (pin "1") (pinfunction "1_1") (pintype "passive"))
      (node (ref "C159") (pin "1") (pinfunction "1_1") (pintype "passive"))
      (node (ref "C161") (pin "1") (pinfunction "1_1") (pintype "passive"))
      (node (ref "C176") (pin "1") (pinfunction "1_1") (pintype "passive"))
      (node (ref "C178") (pin "1") (pinfunction "1_1") (pintype "passive"))
      (node (ref "C89") (pin "1") (pinfunction "1_1") (pintype "passive"))
      (node (ref "C98") (pin "1") (pinfunction "1_1") (pintype "passive"))
      (node (ref "R54") (pin "2") (pinfunction "2_2") (pintype "passive"))
      (node (ref "R55") (pin "2") (pinfunction "2_2") (pintype "passive"))
      (node (ref "U29") (pin "3") (pinfunction "VDD_3") (pintype "power_in"))
      (node (ref "U54") (pin "3") (pinfunction "VIN_3") (pintype "passive"))
      (node (ref "U56") (pin "10") (pinfunction "VDD_10") (pintype "power_in"))
      (node (ref "U57") (pin "10") (pinfunction "VDD_10") (pintype "power_in"))
      (node (ref "U61") (pin "10") (pinfunction "VDD_10") (pintype "power_in"))
      (node (ref "U61") (pin "11") (pinfunction "AD1_11") (pintype "passive"))
      (node (ref "U61") (pin "12") (pinfunction "AD0_12") (pintype "passive"))
      (node (ref "U62") (pin "10") (pinfunction "VDD_10") (pintype "power_in"))
      (node (ref "U62") (pin "12") (pinfunction "AD0_12") (pintype "passive"))
    )
    (net (code "43") (name "unconnected-(T1-Pad1)") (class "Default")
      (node (ref "T1") (pin "1") (pinfunction "1_1") (pintype "passive"))
    )
    (net (code "44") (name "unconnected-(T2-Pad1)") (class "Default")
      (node (ref "T2") (pin "1") (pinfunction "1_1") (pintype "passive"))
    )
    (net (code "45") (name "unconnected-(T3-Pad1)") (class "Default")
      (node (ref "T3") (pin "1") (pinfunction "1_1") (pintype "passive"))
    )
    (net (code "46") (name "unconnected-(T4-Pad1)") (class "Default")
      (node (ref "T4") (pin "1") (pinfunction "1_1") (pintype "passive"))
    )
    (net (code "47") (name "unconnected-(U29-VOUTB-Pad13)") (class "Default")
      (node (ref "U29") (pin "13") (pinfunction "VOUTB_13") (pintype "tri_state+no_connect"))
    )
    (net (code "48") (name "unconnected-(U29-VOUTC-Pad5)") (class "Default")
      (node (ref "U29") (pin "5") (pinfunction "VOUTC_5") (pintype "tri_state+no_connect"))
    )
    (net (code "49") (name "unconnected-(U29-VOUTE-Pad6)") (class "Default")
      (node (ref "U29") (pin "6") (pinfunction "VOUTE_6") (pintype "tri_state+no_connect"))
    )
    (net (code "50") (name "unconnected-(U54-NC-Pad1)") (class "Default")
      (node (ref "U54") (pin "1") (pinfunction "NC_1") (pintype "passive+no_connect"))
    )
    (net (code "51") (name "unconnected-(U54-NC-Pad5)") (class "Default")
      (node (ref "U54") (pin "5") (pinfunction "NC_5") (pintype "passive+no_connect"))
    )
    (net (code "52") (name "unconnected-(U54-NC-Pad6)") (class "Default")
      (node (ref "U54") (pin "6") (pinfunction "NC_6") (pintype "passive+no_connect"))
    )
  )
)
